# Atmega328p_sismin_attempt_3.net
KiCad netlist of a schematic drawn in EAGLE
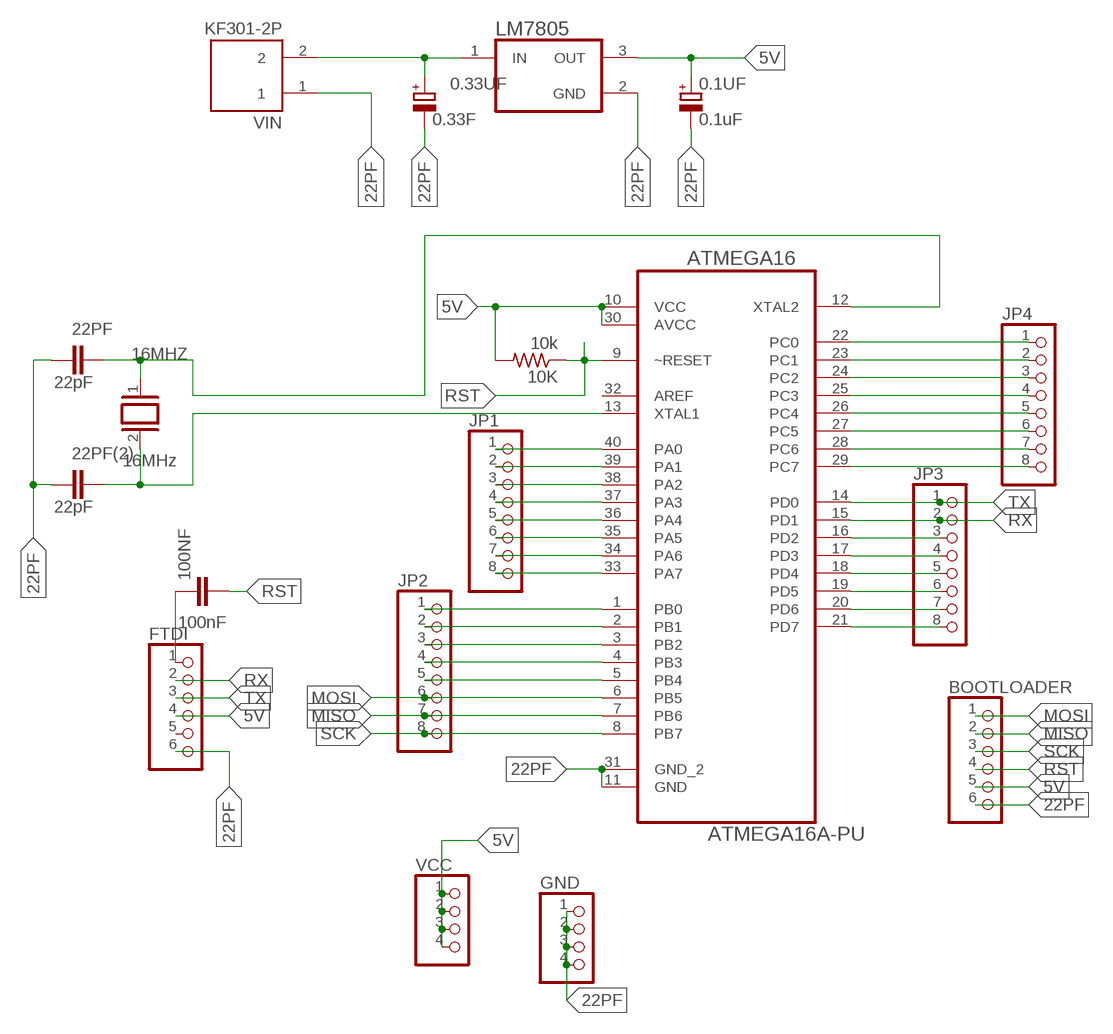
[diagram p0: schematic, sheet 1]

(export (version "E")
  (design (tool "Eeschema 10.0.6"))
  (components
    (comp (ref "0.1UF")
      (value "0.1uF")
      (footprint "eagle-import:E2,5-6")
      (libsource (lib "eagle-import") (part "CPOL-EUE2.5-6"))
    )
    (comp (ref "0.33UF")
      (value "0.33F")
      (footprint "eagle-import:E2,5-6")
      (libsource (lib "eagle-import") (part "CPOL-EUE2.5-6"))
    )
    (comp (ref "10K")
      (value "10k")
      (footprint "eagle-import:0207_7")
      (libsource (lib "eagle-import") (part "R-US_0207/7"))
    )
    (comp (ref "16MHZ")
      (value "16MHz")
      (footprint "eagle-import:QS")
      (libsource (lib "eagle-import") (part "XTAL/S"))
    )
    (comp (ref "22PF")
      (value "22pF")
      (footprint "eagle-import:C2.5-3")
      (libsource (lib "eagle-import") (part "C2,5-3"))
    )
    (comp (ref "22PF(2)")
      (value "22pF")
      (footprint "eagle-import:C2.5-3")
      (libsource (lib "eagle-import") (part "C2,5-3"))
    )
    (comp (ref "100NF")
      (value "100nF")
      (footprint "eagle-import:C050-025X075")
      (libsource (lib "eagle-import") (part "C-EU050-025X075"))
    )
    (comp (ref "ATMEGA16")
      (value "ATMEGA16A-PU")
      (footprint "eagle-import:DIP254P1524X482-40")
      (fields (field (name "MF") "Microchip"))
      (libsource (lib "eagle-import") (part "ATMEGA16A-PU"))
    )
    (comp (ref "BOOTLOADER")
      (value "PINHD-1X6")
      (footprint "eagle-import:1X06")
      (libsource (lib "eagle-import") (part "PINHD-1X6"))
    )
    (comp (ref "FTDI")
      (value "PINHD-1X6")
      (footprint "eagle-import:1X06")
      (libsource (lib "eagle-import") (part "PINHD-1X6"))
    )
    (comp (ref "GND")
      (value "PINHD-1X4")
      (footprint "eagle-import:1X04")
      (libsource (lib "eagle-import") (part "PINHD-1X4"))
    )
    (comp (ref "JP1")
      (value "PINHD-1X8")
      (footprint "eagle-import:1X08")
      (libsource (lib "eagle-import") (part "PINHD-1X8"))
    )
    (comp (ref "JP2")
      (value "PINHD-1X8")
      (footprint "eagle-import:1X08")
      (libsource (lib "eagle-import") (part "PINHD-1X8"))
    )
    (comp (ref "JP3")
      (value "PINHD-1X8")
      (footprint "eagle-import:1X08")
      (libsource (lib "eagle-import") (part "PINHD-1X8"))
    )
    (comp (ref "JP4")
      (value "PINHD-1X8")
      (footprint "eagle-import:1X08")
      (libsource (lib "eagle-import") (part "PINHD-1X8"))
    )
    (comp (ref "LM7805")
      (value "LM7805CT/NOPB")
      (footprint "eagle-import:TO254P1054X470X2600-3")
      (fields (field (name "MF") "ON Semiconductor") (field (name "MP") "LM7805CT"))
      (libsource (lib "eagle-import") (part "LM7805CT/NOPB"))
    )
    (comp (ref "VCC")
      (value "PINHD-1X4")
      (footprint "eagle-import:1X04")
      (libsource (lib "eagle-import") (part "PINHD-1X4"))
    )
    (comp (ref "VIN")
      (value "KF301-2P")
      (footprint "eagle-import:HANDSON_KF301-2P")
      (fields (field (name "MF") "Handson Technology"))
      (libsource (lib "eagle-import") (part "KF301-2P"))
    )
  )
  (nets
    (net (code "1") (name "5V") (class "Default")
      (node (ref "0.1UF") (pin "+") (pinfunction "+_+") (pintype "passive"))
      (node (ref "10K") (pin "2") (pinfunction "2_2") (pintype "passive"))
      (node (ref "ATMEGA16") (pin "10") (pinfunction "VCC_10") (pintype "power_in"))
      (node (ref "ATMEGA16") (pin "30") (pinfunction "AVCC_30") (pintype "power_in"))
      (node (ref "BOOTLOADER") (pin "5") (pinfunction "5_5") (pintype "passive"))
      (node (ref "FTDI") (pin "4") (pinfunction "4_4") (pintype "passive"))
      (node (ref "LM7805") (pin "3") (pinfunction "OUT_3") (pintype "output"))
      (node (ref "VCC") (pin "1") (pinfunction "1_1") (pintype "passive"))
      (node (ref "VCC") (pin "2") (pinfunction "2_2") (pintype "passive"))
      (node (ref "VCC") (pin "3") (pinfunction "3_3") (pintype "passive"))
      (node (ref "VCC") (pin "4") (pinfunction "4_4") (pintype "passive"))
    )
    (net (code "2") (name "22PF") (class "Default")
      (node (ref "0.1UF") (pin "-") (pinfunction "-_-") (pintype "passive"))
      (node (ref "0.33UF") (pin "-") (pinfunction "-_-") (pintype "passive"))
      (node (ref "22PF") (pin "2") (pinfunction "2_2") (pintype "passive"))
      (node (ref "22PF(2)") (pin "2") (pinfunction "2_2") (pintype "passive"))
      (node (ref "ATMEGA16") (pin "11") (pinfunction "GND_11") (pintype "passive"))
      (node (ref "ATMEGA16") (pin "31") (pinfunction "GND_2_31") (pintype "passive"))
      (node (ref "BOOTLOADER") (pin "6") (pinfunction "6_6") (pintype "passive"))
      (node (ref "FTDI") (pin "6") (pinfunction "6_6") (pintype "passive"))
      (node (ref "GND") (pin "1") (pinfunction "1_1") (pintype "passive"))
      (node (ref "GND") (pin "2") (pinfunction "2_2") (pintype "passive"))
      (node (ref "GND") (pin "3") (pinfunction "3_3") (pintype "passive"))
      (node (ref "GND") (pin "4") (pinfunction "4_4") (pintype "passive"))
      (node (ref "LM7805") (pin "2") (pinfunction "GND_2") (pintype "power_in"))
      (node (ref "VIN") (pin "1") (pinfunction "1_1") (pintype "passive"))
    )
    (net (code "3") (name "MISO") (class "Default")
      (node (ref "ATMEGA16") (pin "7") (pinfunction "PB6_7") (pintype "bidirectional"))
      (node (ref "BOOTLOADER") (pin "2") (pinfunction "2_2") (pintype "passive"))
      (node (ref "JP2") (pin "7") (pinfunction "7_7") (pintype "passive"))
    )
    (net (code "4") (name "MOSI") (class "Default")
      (node (ref "ATMEGA16") (pin "6") (pinfunction "PB5_6") (pintype "bidirectional"))
      (node (ref "BOOTLOADER") (pin "1") (pinfunction "1_1") (pintype "passive"))
      (node (ref "JP2") (pin "6") (pinfunction "6_6") (pintype "passive"))
    )
    (net (code "5") (name "Net-(100NF-Pad1)") (class "Default")
      (node (ref "100NF") (pin "1") (pinfunction "1_1") (pintype "passive"))
      (node (ref "FTDI") (pin "1") (pinfunction "1_1") (pintype "passive"))
    )
    (net (code "6") (name "Net-(ATMEGA16-PA0)") (class "Default")
      (node (ref "ATMEGA16") (pin "40") (pinfunction "PA0_40") (pintype "bidirectional"))
      (node (ref "JP1") (pin "1") (pinfunction "1_1") (pintype "passive"))
    )
    (net (code "7") (name "Net-(ATMEGA16-PA1)") (class "Default")
      (node (ref "ATMEGA16") (pin "39") (pinfunction "PA1_39") (pintype "bidirectional"))
      (node (ref "JP1") (pin "2") (pinfunction "2_2") (pintype "passive"))
    )
    (net (code "8") (name "Net-(ATMEGA16-PA2)") (class "Default")
      (node (ref "ATMEGA16") (pin "38") (pinfunction "PA2_38") (pintype "bidirectional"))
      (node (ref "JP1") (pin "3") (pinfunction "3_3") (pintype "passive"))
    )
    (net (code "9") (name "Net-(ATMEGA16-PA3)") (class "Default")
      (node (ref "ATMEGA16") (pin "37") (pinfunction "PA3_37") (pintype "bidirectional"))
      (node (ref "JP1") (pin "4") (pinfunction "4_4") (pintype "passive"))
    )
    (net (code "10") (name "Net-(ATMEGA16-PA4)") (class "Default")
      (node (ref "ATMEGA16") (pin "36") (pinfunction "PA4_36") (pintype "bidirectional"))
      (node (ref "JP1") (pin "5") (pinfunction "5_5") (pintype "passive"))
    )
    (net (code "11") (name "Net-(ATMEGA16-PA5)") (class "Default")
      (node (ref "ATMEGA16") (pin "35") (pinfunction "PA5_35") (pintype "bidirectional"))
      (node (ref "JP1") (pin "6") (pinfunction "6_6") (pintype "passive"))
    )
    (net (code "12") (name "Net-(ATMEGA16-PA6)") (class "Default")
      (node (ref "ATMEGA16") (pin "34") (pinfunction "PA6_34") (pintype "bidirectional"))
      (node (ref "JP1") (pin "7") (pinfunction "7_7") (pintype "passive"))
    )
    (net (code "13") (name "Net-(ATMEGA16-PA7)") (class "Default")
      (node (ref "ATMEGA16") (pin "33") (pinfunction "PA7_33") (pintype "bidirectional"))
      (node (ref "JP1") (pin "8") (pinfunction "8_8") (pintype "passive"))
    )
    (net (code "14") (name "Net-(ATMEGA16-PB0)") (class "Default")
      (node (ref "ATMEGA16") (pin "1") (pinfunction "PB0_1") (pintype "bidirectional"))
      (node (ref "JP2") (pin "1") (pinfunction "1_1") (pintype "passive"))
    )
    (net (code "15") (name "Net-(ATMEGA16-PB1)") (class "Default")
      (node (ref "ATMEGA16") (pin "2") (pinfunction "PB1_2") (pintype "bidirectional"))
      (node (ref "JP2") (pin "2") (pinfunction "2_2") (pintype "passive"))
    )
    (net (code "16") (name "Net-(ATMEGA16-PB2)") (class "Default")
      (node (ref "ATMEGA16") (pin "3") (pinfunction "PB2_3") (pintype "bidirectional"))
      (node (ref "JP2") (pin "3") (pinfunction "3_3") (pintype "passive"))
    )
    (net (code "17") (name "Net-(ATMEGA16-PB3)") (class "Default")
      (node (ref "ATMEGA16") (pin "4") (pinfunction "PB3_4") (pintype "bidirectional"))
      (node (ref "JP2") (pin "4") (pinfunction "4_4") (pintype "passive"))
    )
    (net (code "18") (name "Net-(ATMEGA16-PB4)") (class "Default")
      (node (ref "ATMEGA16") (pin "5") (pinfunction "PB4_5") (pintype "bidirectional"))
      (node (ref "JP2") (pin "5") (pinfunction "5_5") (pintype "passive"))
    )
    (net (code "19") (name "Net-(ATMEGA16-PC0)") (class "Default")
      (node (ref "ATMEGA16") (pin "22") (pinfunction "PC0_22") (pintype "bidirectional"))
      (node (ref "JP4") (pin "1") (pinfunction "1_1") (pintype "passive"))
    )
    (net (code "20") (name "Net-(ATMEGA16-PC1)") (class "Default")
      (node (ref "ATMEGA16") (pin "23") (pinfunction "PC1_23") (pintype "bidirectional"))
      (node (ref "JP4") (pin "2") (pinfunction "2_2") (pintype "passive"))
    )
    (net (code "21") (name "Net-(ATMEGA16-PC2)") (class "Default")
      (node (ref "ATMEGA16") (pin "24") (pinfunction "PC2_24") (pintype "bidirectional"))
      (node (ref "JP4") (pin "3") (pinfunction "3_3") (pintype "passive"))
    )
    (net (code "22") (name "Net-(ATMEGA16-PC3)") (class "Default")
      (node (ref "ATMEGA16") (pin "25") (pinfunction "PC3_25") (pintype "bidirectional"))
      (node (ref "JP4") (pin "4") (pinfunction "4_4") (pintype "passive"))
    )
    (net (code "23") (name "Net-(ATMEGA16-PC4)") (class "Default")
      (node (ref "ATMEGA16") (pin "26") (pinfunction "PC4_26") (pintype "bidirectional"))
      (node (ref "JP4") (pin "5") (pinfunction "5_5") (pintype "passive"))
    )
    (net (code "24") (name "Net-(ATMEGA16-PC5)") (class "Default")
      (node (ref "ATMEGA16") (pin "27") (pinfunction "PC5_27") (pintype "bidirectional"))
      (node (ref "JP4") (pin "6") (pinfunction "6_6") (pintype "passive"))
    )
    (net (code "25") (name "Net-(ATMEGA16-PC6)") (class "Default")
      (node (ref "ATMEGA16") (pin "28") (pinfunction "PC6_28") (pintype "bidirectional"))
      (node (ref "JP4") (pin "7") (pinfunction "7_7") (pintype "passive"))
    )
    (net (code "26") (name "Net-(ATMEGA16-PC7)") (class "Default")
      (node (ref "ATMEGA16") (pin "29") (pinfunction "PC7_29") (pintype "bidirectional"))
      (node (ref "JP4") (pin "8") (pinfunction "8_8") (pintype "passive"))
    )
    (net (code "27") (name "Net-(ATMEGA16-PD2)") (class "Default")
      (node (ref "ATMEGA16") (pin "16") (pinfunction "PD2_16") (pintype "bidirectional"))
      (node (ref "JP3") (pin "3") (pinfunction "3_3") (pintype "passive"))
    )
    (net (code "28") (name "Net-(ATMEGA16-PD3)") (class "Default")
      (node (ref "ATMEGA16") (pin "17") (pinfunction "PD3_17") (pintype "bidirectional"))
      (node (ref "JP3") (pin "4") (pinfunction "4_4") (pintype "passive"))
    )
    (net (code "29") (name "Net-(ATMEGA16-PD4)") (class "Default")
      (node (ref "ATMEGA16") (pin "18") (pinfunction "PD4_18") (pintype "bidirectional"))
      (node (ref "JP3") (pin "5") (pinfunction "5_5") (pintype "passive"))
    )
    (net (code "30") (name "Net-(ATMEGA16-PD5)") (class "Default")
      (node (ref "ATMEGA16") (pin "19") (pinfunction "PD5_19") (pintype "bidirectional"))
      (node (ref "JP3") (pin "6") (pinfunction "6_6") (pintype "passive"))
    )
    (net (code "31") (name "Net-(ATMEGA16-PD6)") (class "Default")
      (node (ref "ATMEGA16") (pin "20") (pinfunction "PD6_20") (pintype "bidirectional"))
      (node (ref "JP3") (pin "7") (pinfunction "7_7") (pintype "passive"))
    )
    (net (code "32") (name "Net-(ATMEGA16-PD7)") (class "Default")
      (node (ref "ATMEGA16") (pin "21") (pinfunction "PD7_21") (pintype "bidirectional"))
      (node (ref "JP3") (pin "8") (pinfunction "8_8") (pintype "passive"))
    )
    (net (code "33") (name "Net-(ATMEGA16-XTAL1)") (class "Default")
      (node (ref "16MHZ") (pin "2") (pinfunction "2_2") (pintype "passive"))
      (node (ref "22PF(2)") (pin "1") (pinfunction "1_1") (pintype "passive"))
      (node (ref "ATMEGA16") (pin "13") (pinfunction "XTAL1_13") (pintype "input"))
    )
    (net (code "34") (name "Net-(ATMEGA16-XTAL2)") (class "Default")
      (node (ref "16MHZ") (pin "1") (pinfunction "1_1") (pintype "passive"))
      (node (ref "22PF") (pin "1") (pinfunction "1_1") (pintype "passive"))
      (node (ref "ATMEGA16") (pin "12") (pinfunction "XTAL2_12") (pintype "output"))
    )
    (net (code "35") (name "Net-(LM7805-IN)") (class "Default")
      (node (ref "0.33UF") (pin "+") (pinfunction "+_+") (pintype "passive"))
      (node (ref "LM7805") (pin "1") (pinfunction "IN_1") (pintype "input"))
      (node (ref "VIN") (pin "2") (pinfunction "2_2") (pintype "passive"))
    )
    (net (code "36") (name "RST") (class "Default")
      (node (ref "100NF") (pin "2") (pinfunction "2_2") (pintype "passive"))
      (node (ref "10K") (pin "1") (pinfunction "1_1") (pintype "passive"))
      (node (ref "ATMEGA16") (pin "9") (pinfunction "~{RESET}_9") (pintype "input"))
      (node (ref "BOOTLOADER") (pin "4") (pinfunction "4_4") (pintype "passive"))
    )
    (net (code "37") (name "RX") (class "Default")
      (node (ref "ATMEGA16") (pin "15") (pinfunction "PD1_15") (pintype "bidirectional"))
      (node (ref "FTDI") (pin "2") (pinfunction "2_2") (pintype "passive"))
      (node (ref "JP3") (pin "2") (pinfunction "2_2") (pintype "passive"))
    )
    (net (code "38") (name "SCK") (class "Default")
      (node (ref "ATMEGA16") (pin "8") (pinfunction "PB7_8") (pintype "bidirectional"))
      (node (ref "BOOTLOADER") (pin "3") (pinfunction "3_3") (pintype "passive"))
      (node (ref "JP2") (pin "8") (pinfunction "8_8") (pintype "passive"))
    )
    (net (code "39") (name "TX") (class "Default")
      (node (ref "ATMEGA16") (pin "14") (pinfunction "PD0_14") (pintype "bidirectional"))
      (node (ref "FTDI") (pin "3") (pinfunction "3_3") (pintype "passive"))
      (node (ref "JP3") (pin "1") (pinfunction "1_1") (pintype "passive"))
    )
    (net (code "40") (name "unconnected-(ATMEGA16-AREF-Pad32)") (class "Default")
      (node (ref "ATMEGA16") (pin "32") (pinfunction "AREF_32") (pintype "input"))
    )
    (net (code "41") (name "unconnected-(FTDI-Pad5)") (class "Default")
      (node (ref "FTDI") (pin "5") (pinfunction "5_5") (pintype "passive"))
    )
  )
)
